# LED_STRIP.net
KiCad netlist of a schematic drawn in EAGLE
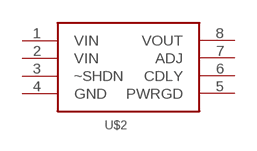
[diagram p0: schematic, sheet 1, part 1 of 2]
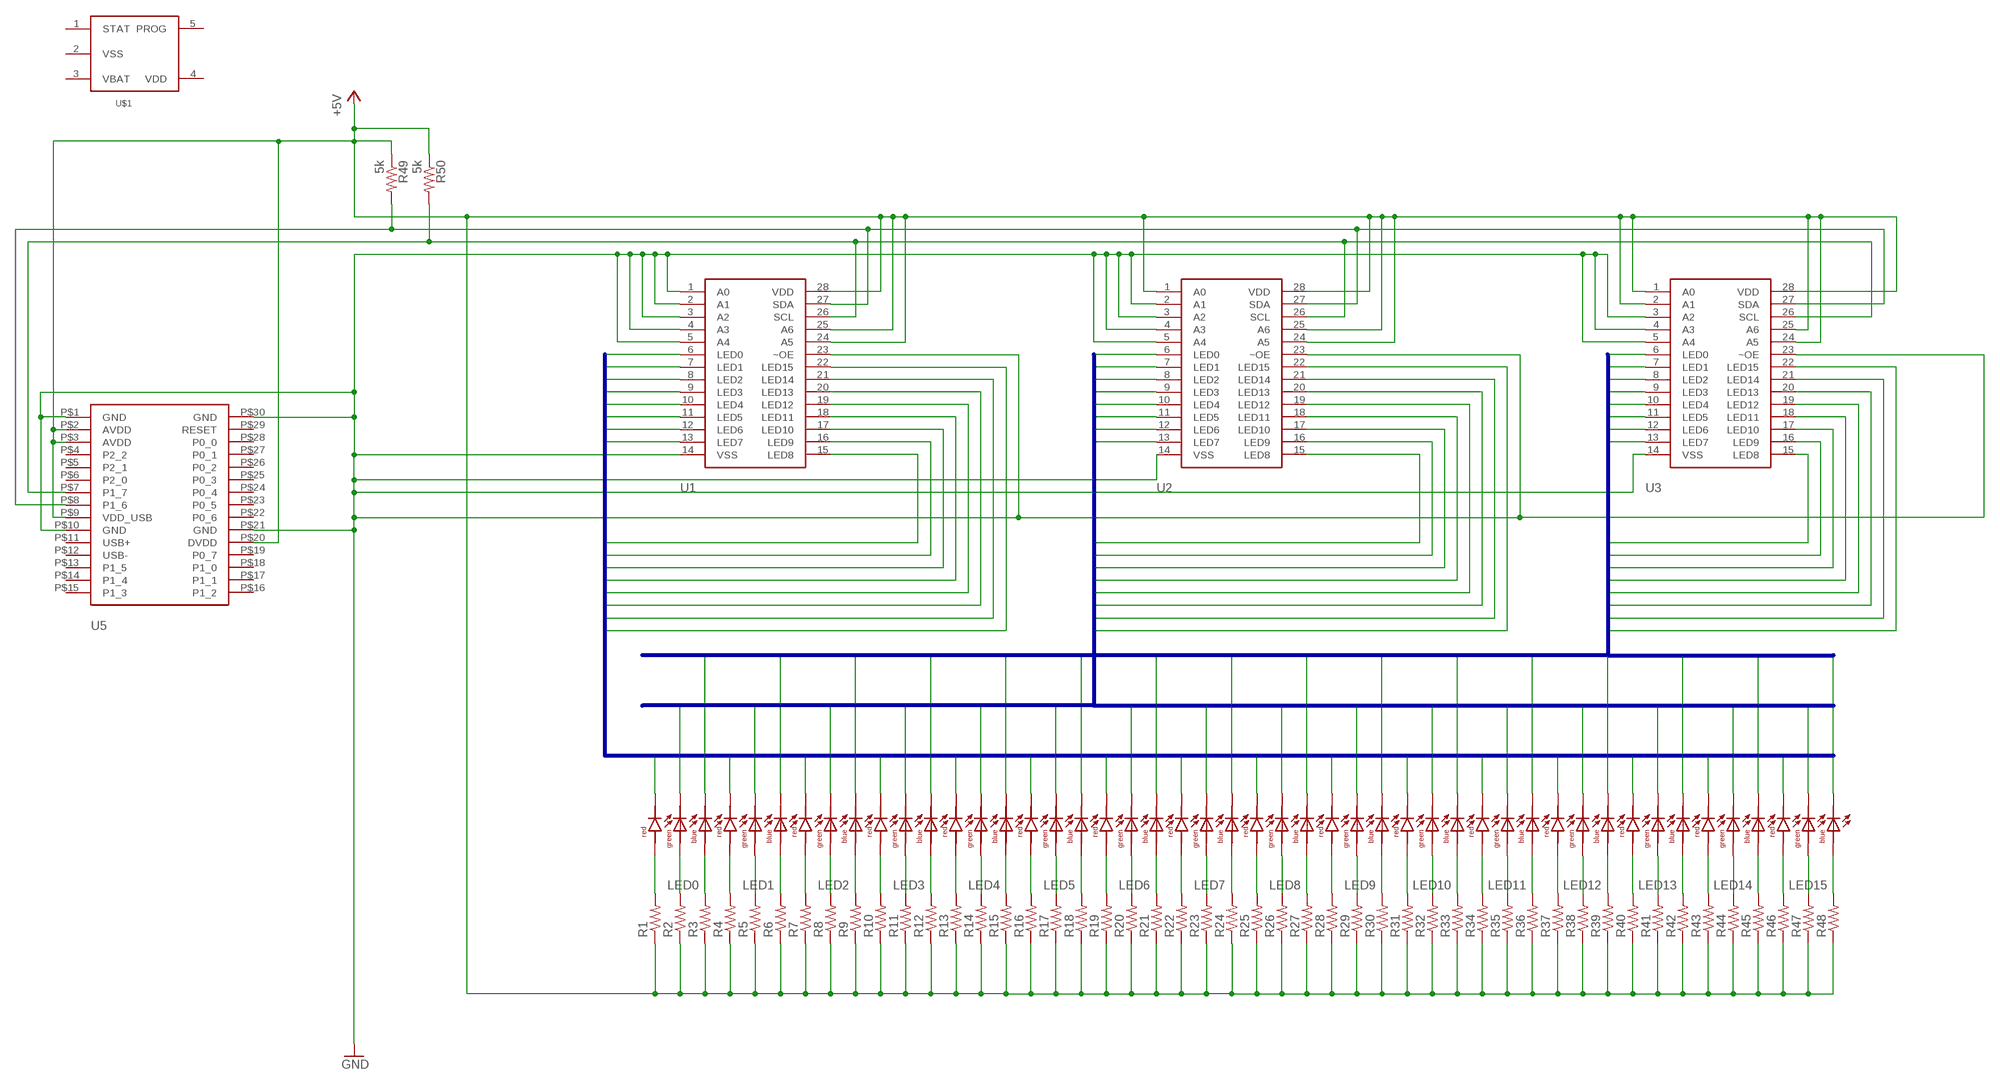
[diagram p1: schematic, sheet 1, part 2 of 2]

(export (version "E")
  (design (tool "Eeschema 10.0.6"))
  (components
    (comp (ref "LED0")
      (value "LED_RGB")
      (footprint "eagle-import:6-PLCC")
      (libsource (lib "eagle-import") (part "LED_RGB"))
    )
    (comp (ref "LED1")
      (value "LED_RGB")
      (footprint "eagle-import:6-PLCC")
      (libsource (lib "eagle-import") (part "LED_RGB"))
    )
    (comp (ref "LED2")
      (value "LED_RGB")
      (footprint "eagle-import:6-PLCC")
      (libsource (lib "eagle-import") (part "LED_RGB"))
    )
    (comp (ref "LED3")
      (value "LED_RGB")
      (footprint "eagle-import:6-PLCC")
      (libsource (lib "eagle-import") (part "LED_RGB"))
    )
    (comp (ref "LED4")
      (value "LED_RGB")
      (footprint "eagle-import:6-PLCC")
      (libsource (lib "eagle-import") (part "LED_RGB"))
    )
    (comp (ref "LED5")
      (value "LED_RGB")
      (footprint "eagle-import:6-PLCC")
      (libsource (lib "eagle-import") (part "LED_RGB"))
    )
    (comp (ref "LED6")
      (value "LED_RGB")
      (footprint "eagle-import:6-PLCC")
      (libsource (lib "eagle-import") (part "LED_RGB"))
    )
    (comp (ref "LED7")
      (value "LED_RGB")
      (footprint "eagle-import:6-PLCC")
      (libsource (lib "eagle-import") (part "LED_RGB"))
    )
    (comp (ref "LED8")
      (value "LED_RGB")
      (footprint "eagle-import:6-PLCC")
      (libsource (lib "eagle-import") (part "LED_RGB"))
    )
    (comp (ref "LED9")
      (value "LED_RGB")
      (footprint "eagle-import:6-PLCC")
      (libsource (lib "eagle-import") (part "LED_RGB"))
    )
    (comp (ref "LED10")
      (value "LED_RGB")
      (footprint "eagle-import:6-PLCC")
      (libsource (lib "eagle-import") (part "LED_RGB"))
    )
    (comp (ref "LED11")
      (value "LED_RGB")
      (footprint "eagle-import:6-PLCC")
      (libsource (lib "eagle-import") (part "LED_RGB"))
    )
    (comp (ref "LED12")
      (value "LED_RGB")
      (footprint "eagle-import:6-PLCC")
      (libsource (lib "eagle-import") (part "LED_RGB"))
    )
    (comp (ref "LED13")
      (value "LED_RGB")
      (footprint "eagle-import:6-PLCC")
      (libsource (lib "eagle-import") (part "LED_RGB"))
    )
    (comp (ref "LED14")
      (value "LED_RGB")
      (footprint "eagle-import:6-PLCC")
      (libsource (lib "eagle-import") (part "LED_RGB"))
    )
    (comp (ref "LED15")
      (value "LED_RGB")
      (footprint "eagle-import:6-PLCC")
      (libsource (lib "eagle-import") (part "LED_RGB"))
    )
    (comp (ref "R1")
      (value "R0402")
      (footprint "eagle-import:0402")
      (libsource (lib "eagle-import") (part "R0402"))
    )
    (comp (ref "R2")
      (value "R0402")
      (footprint "eagle-import:0402")
      (libsource (lib "eagle-import") (part "R0402"))
    )
    (comp (ref "R3")
      (value "R0402")
      (footprint "eagle-import:0402")
      (libsource (lib "eagle-import") (part "R0402"))
    )
    (comp (ref "R4")
      (value "R0402")
      (footprint "eagle-import:0402")
      (libsource (lib "eagle-import") (part "R0402"))
    )
    (comp (ref "R5")
      (value "R0402")
      (footprint "eagle-import:0402")
      (libsource (lib "eagle-import") (part "R0402"))
    )
    (comp (ref "R6")
      (value "R0402")
      (footprint "eagle-import:0402")
      (libsource (lib "eagle-import") (part "R0402"))
    )
    (comp (ref "R7")
      (value "R0402")
      (footprint "eagle-import:0402")
      (libsource (lib "eagle-import") (part "R0402"))
    )
    (comp (ref "R8")
      (value "R0402")
      (footprint "eagle-import:0402")
      (libsource (lib "eagle-import") (part "R0402"))
    )
    (comp (ref "R9")
      (value "R0402")
      (footprint "eagle-import:0402")
      (libsource (lib "eagle-import") (part "R0402"))
    )
    (comp (ref "R10")
      (value "R0402")
      (footprint "eagle-import:0402")
      (libsource (lib "eagle-import") (part "R0402"))
    )
    (comp (ref "R11")
      (value "R0402")
      (footprint "eagle-import:0402")
      (libsource (lib "eagle-import") (part "R0402"))
    )
    (comp (ref "R12")
      (value "R0402")
      (footprint "eagle-import:0402")
      (libsource (lib "eagle-import") (part "R0402"))
    )
    (comp (ref "R13")
      (value "R0402")
      (footprint "eagle-import:0402")
      (libsource (lib "eagle-import") (part "R0402"))
    )
    (comp (ref "R14")
      (value "R0402")
      (footprint "eagle-import:0402")
      (libsource (lib "eagle-import") (part "R0402"))
    )
    (comp (ref "R15")
      (value "R0402")
      (footprint "eagle-import:0402")
      (libsource (lib "eagle-import") (part "R0402"))
    )
    (comp (ref "R16")
      (value "R0402")
      (footprint "eagle-import:0402")
      (libsource (lib "eagle-import") (part "R0402"))
    )
    (comp (ref "R17")
      (value "R0402")
      (footprint "eagle-import:0402")
      (libsource (lib "eagle-import") (part "R0402"))
    )
    (comp (ref "R18")
      (value "R0402")
      (footprint "eagle-import:0402")
      (libsource (lib "eagle-import") (part "R0402"))
    )
    (comp (ref "R19")
      (value "R0402")
      (footprint "eagle-import:0402")
      (libsource (lib "eagle-import") (part "R0402"))
    )
    (comp (ref "R20")
      (value "R0402")
      (footprint "eagle-import:0402")
      (libsource (lib "eagle-import") (part "R0402"))
    )
    (comp (ref "R21")
      (value "R0402")
      (footprint "eagle-import:0402")
      (libsource (lib "eagle-import") (part "R0402"))
    )
    (comp (ref "R22")
      (value "R0402")
      (footprint "eagle-import:0402")
      (libsource (lib "eagle-import") (part "R0402"))
    )
    (comp (ref "R23")
      (value "R0402")
      (footprint "eagle-import:0402")
      (libsource (lib "eagle-import") (part "R0402"))
    )
    (comp (ref "R24")
      (value "R0402")
      (footprint "eagle-import:0402")
      (libsource (lib "eagle-import") (part "R0402"))
    )
    (comp (ref "R25")
      (value "R0402")
      (footprint "eagle-import:0402")
      (libsource (lib "eagle-import") (part "R0402"))
    )
    (comp (ref "R26")
      (value "R0402")
      (footprint "eagle-import:0402")
      (libsource (lib "eagle-import") (part "R0402"))
    )
    (comp (ref "R27")
      (value "R0402")
      (footprint "eagle-import:0402")
      (libsource (lib "eagle-import") (part "R0402"))
    )
    (comp (ref "R28")
      (value "R0402")
      (footprint "eagle-import:0402")
      (libsource (lib "eagle-import") (part "R0402"))
    )
    (comp (ref "R29")
      (value "R0402")
      (footprint "eagle-import:0402")
      (libsource (lib "eagle-import") (part "R0402"))
    )
    (comp (ref "R30")
      (value "R0402")
      (footprint "eagle-import:0402")
      (libsource (lib "eagle-import") (part "R0402"))
    )
    (comp (ref "R31")
      (value "R0402")
      (footprint "eagle-import:0402")
      (libsource (lib "eagle-import") (part "R0402"))
    )
    (comp (ref "R32")
      (value "R0402")
      (footprint "eagle-import:0402")
      (libsource (lib "eagle-import") (part "R0402"))
    )
    (comp (ref "R33")
      (value "R0402")
      (footprint "eagle-import:0402")
      (libsource (lib "eagle-import") (part "R0402"))
    )
    (comp (ref "R34")
      (value "R0402")
      (footprint "eagle-import:0402")
      (libsource (lib "eagle-import") (part "R0402"))
    )
    (comp (ref "R35")
      (value "R0402")
      (footprint "eagle-import:0402")
      (libsource (lib "eagle-import") (part "R0402"))
    )
    (comp (ref "R36")
      (value "R0402")
      (footprint "eagle-import:0402")
      (libsource (lib "eagle-import") (part "R0402"))
    )
    (comp (ref "R37")
      (value "R0402")
      (footprint "eagle-import:0402")
      (libsource (lib "eagle-import") (part "R0402"))
    )
    (comp (ref "R38")
      (value "R0402")
      (footprint "eagle-import:0402")
      (libsource (lib "eagle-import") (part "R0402"))
    )
    (comp (ref "R39")
      (value "R0402")
      (footprint "eagle-import:0402")
      (libsource (lib "eagle-import") (part "R0402"))
    )
    (comp (ref "R40")
      (value "R0402")
      (footprint "eagle-import:0402")
      (libsource (lib "eagle-import") (part "R0402"))
    )
    (comp (ref "R41")
      (value "R0402")
      (footprint "eagle-import:0402")
      (libsource (lib "eagle-import") (part "R0402"))
    )
    (comp (ref "R42")
      (value "R0402")
      (footprint "eagle-import:0402")
      (libsource (lib "eagle-import") (part "R0402"))
    )
    (comp (ref "R43")
      (value "R0402")
      (footprint "eagle-import:0402")
      (libsource (lib "eagle-import") (part "R0402"))
    )
    (comp (ref "R44")
      (value "R0402")
      (footprint "eagle-import:0402")
      (libsource (lib "eagle-import") (part "R0402"))
    )
    (comp (ref "R45")
      (value "R0402")
      (footprint "eagle-import:0402")
      (libsource (lib "eagle-import") (part "R0402"))
    )
    (comp (ref "R46")
      (value "R0402")
      (footprint "eagle-import:0402")
      (libsource (lib "eagle-import") (part "R0402"))
    )
    (comp (ref "R47")
      (value "R0402")
      (footprint "eagle-import:0402")
      (libsource (lib "eagle-import") (part "R0402"))
    )
    (comp (ref "R48")
      (value "R0402")
      (footprint "eagle-import:0402")
      (libsource (lib "eagle-import") (part "R0402"))
    )
    (comp (ref "R49")
      (value "5k")
      (footprint "eagle-import:0402")
      (libsource (lib "eagle-import") (part "R0402"))
    )
    (comp (ref "R50")
      (value "5k")
      (footprint "eagle-import:0402")
      (libsource (lib "eagle-import") (part "R0402"))
    )
    (comp (ref "U$1")
      (value "MCP73831")
      (footprint "eagle-import:SOT-23")
      (libsource (lib "eagle-import") (part "MCP73831"))
    )
    (comp (ref "U$2")
      (value "MCP1727")
      (footprint "eagle-import:8-SOIC")
      (libsource (lib "eagle-import") (part "MCP1727"))
    )
    (comp (ref "U1")
      (value "PCA9635")
      (footprint "eagle-import:TSSOP28")
      (libsource (lib "eagle-import") (part "PCA9635"))
    )
    (comp (ref "U2")
      (value "PCA9635")
      (footprint "eagle-import:TSSOP28")
      (libsource (lib "eagle-import") (part "PCA9635"))
    )
    (comp (ref "U3")
      (value "PCA9635")
      (footprint "eagle-import:TSSOP28")
      (libsource (lib "eagle-import") (part "PCA9635"))
    )
    (comp (ref "U5")
      (value "BLE112")
      (footprint "eagle-import:BLE112")
      (libsource (lib "eagle-import") (part "BLE112"))
    )
  )
  (nets
    (net (code "1") (name "+5V") (class "Default")
      (node (ref "R1") (pin "P$1") (pinfunction "1_P$1") (pintype "passive"))
      (node (ref "R10") (pin "P$1") (pinfunction "1_P$1") (pintype "passive"))
      (node (ref "R11") (pin "P$1") (pinfunction "1_P$1") (pintype "passive"))
      (node (ref "R12") (pin "P$1") (pinfunction "1_P$1") (pintype "passive"))
      (node (ref "R13") (pin "P$1") (pinfunction "1_P$1") (pintype "passive"))
      (node (ref "R14") (pin "P$1") (pinfunction "1_P$1") (pintype "passive"))
      (node (ref "R15") (pin "P$1") (pinfunction "1_P$1") (pintype "passive"))
      (node (ref "R16") (pin "P$1") (pinfunction "1_P$1") (pintype "passive"))
      (node (ref "R17") (pin "P$1") (pinfunction "1_P$1") (pintype "passive"))
      (node (ref "R18") (pin "P$1") (pinfunction "1_P$1") (pintype "passive"))
      (node (ref "R19") (pin "P$1") (pinfunction "1_P$1") (pintype "passive"))
      (node (ref "R2") (pin "P$1") (pinfunction "1_P$1") (pintype "passive"))
      (node (ref "R20") (pin "P$1") (pinfunction "1_P$1") (pintype "passive"))
      (node (ref "R21") (pin "P$1") (pinfunction "1_P$1") (pintype "passive"))
      (node (ref "R22") (pin "P$1") (pinfunction "1_P$1") (pintype "passive"))
      (node (ref "R23") (pin "P$1") (pinfunction "1_P$1") (pintype "passive"))
      (node (ref "R24") (pin "P$1") (pinfunction "1_P$1") (pintype "passive"))
      (node (ref "R25") (pin "P$1") (pinfunction "1_P$1") (pintype "passive"))
      (node (ref "R26") (pin "P$1") (pinfunction "1_P$1") (pintype "passive"))
      (node (ref "R27") (pin "P$1") (pinfunction "1_P$1") (pintype "passive"))
      (node (ref "R28") (pin "P$1") (pinfunction "1_P$1") (pintype "passive"))
      (node (ref "R29") (pin "P$1") (pinfunction "1_P$1") (pintype "passive"))
      (node (ref "R3") (pin "P$1") (pinfunction "1_P$1") (pintype "passive"))
      (node (ref "R30") (pin "P$1") (pinfunction "1_P$1") (pintype "passive"))
      (node (ref "R31") (pin "P$1") (pinfunction "1_P$1") (pintype "passive"))
      (node (ref "R32") (pin "P$1") (pinfunction "1_P$1") (pintype "passive"))
      (node (ref "R33") (pin "P$1") (pinfunction "1_P$1") (pintype "passive"))
      (node (ref "R34") (pin "P$1") (pinfunction "1_P$1") (pintype "passive"))
      (node (ref "R35") (pin "P$1") (pinfunction "1_P$1") (pintype "passive"))
      (node (ref "R36") (pin "P$1") (pinfunction "1_P$1") (pintype "passive"))
      (node (ref "R37") (pin "P$1") (pinfunction "1_P$1") (pintype "passive"))
      (node (ref "R38") (pin "P$1") (pinfunction "1_P$1") (pintype "passive"))
      (node (ref "R39") (pin "P$1") (pinfunction "1_P$1") (pintype "passive"))
      (node (ref "R4") (pin "P$1") (pinfunction "1_P$1") (pintype "passive"))
      (node (ref "R40") (pin "P$1") (pinfunction "1_P$1") (pintype "passive"))
      (node (ref "R41") (pin "P$1") (pinfunction "1_P$1") (pintype "passive"))
      (node (ref "R42") (pin "P$1") (pinfunction "1_P$1") (pintype "passive"))
      (node (ref "R43") (pin "P$1") (pinfunction "1_P$1") (pintype "passive"))
      (node (ref "R44") (pin "P$1") (pinfunction "1_P$1") (pintype "passive"))
      (node (ref "R45") (pin "P$1") (pinfunction "1_P$1") (pintype "passive"))
      (node (ref "R46") (pin "P$1") (pinfunction "1_P$1") (pintype "passive"))
      (node (ref "R47") (pin "P$1") (pinfunction "1_P$1") (pintype "passive"))
      (node (ref "R48") (pin "P$1") (pinfunction "1_P$1") (pintype "passive"))
      (node (ref "R49") (pin "P$1") (pinfunction "1_P$1") (pintype "passive"))
      (node (ref "R5") (pin "P$1") (pinfunction "1_P$1") (pintype "passive"))
      (node (ref "R50") (pin "P$1") (pinfunction "1_P$1") (pintype "passive"))
      (node (ref "R6") (pin "P$1") (pinfunction "1_P$1") (pintype "passive"))
      (node (ref "R7") (pin "P$1") (pinfunction "1_P$1") (pintype "passive"))
      (node (ref "R8") (pin "P$1") (pinfunction "1_P$1") (pintype "passive"))
      (node (ref "R9") (pin "P$1") (pinfunction "1_P$1") (pintype "passive"))
      (node (ref "U1") (pin "24") (pinfunction "A5_24") (pintype "bidirectional"))
      (node (ref "U1") (pin "25") (pinfunction "A6_25") (pintype "bidirectional"))
      (node (ref "U1") (pin "28") (pinfunction "VDD_28") (pintype "bidirectional"))
      (node (ref "U2") (pin "1") (pinfunction "A0_1") (pintype "bidirectional"))
      (node (ref "U2") (pin "24") (pinfunction "A5_24") (pintype "bidirectional"))
      (node (ref "U2") (pin "25") (pinfunction "A6_25") (pintype "bidirectional"))
      (node (ref "U2") (pin "28") (pinfunction "VDD_28") (pintype "bidirectional"))
      (node (ref "U3") (pin "1") (pinfunction "A0_1") (pintype "bidirectional"))
      (node (ref "U3") (pin "2") (pinfunction "A1_2") (pintype "bidirectional"))
      (node (ref "U3") (pin "24") (pinfunction "A5_24") (pintype "bidirectional"))
      (node (ref "U3") (pin "25") (pinfunction "A6_25") (pintype "bidirectional"))
      (node (ref "U3") (pin "28") (pinfunction "VDD_28") (pintype "bidirectional"))
      (node (ref "U5") (pin "P$2") (pinfunction "AVDD_P$2") (pintype "bidirectional"))
      (node (ref "U5") (pin "P$20") (pinfunction "DVDD_P$20") (pintype "bidirectional"))
      (node (ref "U5") (pin "P$3") (pinfunction "AVDD_P$3") (pintype "bidirectional"))
      (node (ref "U5") (pin "P$9") (pinfunction "VDD_USB_P$9") (pintype "bidirectional"))
    )
    (net (code "2") (name "/BLUE0") (class "Default")
      (node (ref "LED0") (pin "1") (pinfunction "1_1") (pintype "passive"))
      (node (ref "U3") (pin "6") (pinfunction "LED0_6") (pintype "bidirectional"))
    )
    (net (code "3") (name "/BLUE1") (class "Default")
      (node (ref "LED1") (pin "1") (pinfunction "1_1") (pintype "passive"))
      (node (ref "U3") (pin "7") (pinfunction "LED1_7") (pintype "bidirectional"))
    )
    (net (code "4") (name "/BLUE2") (class "Default")
      (node (ref "LED2") (pin "1") (pinfunction "1_1") (pintype "passive"))
      (node (ref "U3") (pin "8") (pinfunction "LED2_8") (pintype "bidirectional"))
    )
    (net (code "5") (name "/BLUE3") (class "Default")
      (node (ref "LED3") (pin "1") (pinfunction "1_1") (pintype "passive"))
      (node (ref "U3") (pin "9") (pinfunction "LED3_9") (pintype "bidirectional"))
    )
    (net (code "6") (name "/BLUE4") (class "Default")
      (node (ref "LED4") (pin "1") (pinfunction "1_1") (pintype "passive"))
      (node (ref "U3") (pin "10") (pinfunction "LED4_10") (pintype "bidirectional"))
    )
    (net (code "7") (name "/BLUE5") (class "Default")
      (node (ref "LED5") (pin "1") (pinfunction "1_1") (pintype "passive"))
      (node (ref "U3") (pin "11") (pinfunction "LED5_11") (pintype "bidirectional"))
    )
    (net (code "8") (name "/BLUE6") (class "Default")
      (node (ref "LED6") (pin "1") (pinfunction "1_1") (pintype "passive"))
      (node (ref "U3") (pin "12") (pinfunction "LED6_12") (pintype "bidirectional"))
    )
    (net (code "9") (name "/BLUE7") (class "Default")
      (node (ref "LED7") (pin "1") (pinfunction "1_1") (pintype "passive"))
      (node (ref "U3") (pin "13") (pinfunction "LED7_13") (pintype "bidirectional"))
    )
    (net (code "10") (name "/BLUE8") (class "Default")
      (node (ref "LED8") (pin "1") (pinfunction "1_1") (pintype "passive"))
      (node (ref "U3") (pin "15") (pinfunction "LED8_15") (pintype "bidirectional"))
    )
    (net (code "11") (name "/BLUE9") (class "Default")
      (node (ref "LED9") (pin "1") (pinfunction "1_1") (pintype "passive"))
      (node (ref "U3") (pin "16") (pinfunction "LED9_16") (pintype "bidirectional"))
    )
    (net (code "12") (name "/BLUE10") (class "Default")
      (node (ref "LED10") (pin "1") (pinfunction "1_1") (pintype "passive"))
      (node (ref "U3") (pin "17") (pinfunction "LED10_17") (pintype "bidirectional"))
    )
    (net (code "13") (name "/BLUE11") (class "Default")
      (node (ref "LED11") (pin "1") (pinfunction "1_1") (pintype "passive"))
      (node (ref "U3") (pin "18") (pinfunction "LED11_18") (pintype "bidirectional"))
    )
    (net (code "14") (name "/BLUE12") (class "Default")
      (node (ref "LED12") (pin "1") (pinfunction "1_1") (pintype "passive"))
      (node (ref "U3") (pin "19") (pinfunction "LED12_19") (pintype "bidirectional"))
    )
    (net (code "15") (name "/BLUE13") (class "Default")
      (node (ref "LED13") (pin "1") (pinfunction "1_1") (pintype "passive"))
      (node (ref "U3") (pin "20") (pinfunction "LED13_20") (pintype "bidirectional"))
    )
    (net (code "16") (name "/BLUE14") (class "Default")
      (node (ref "LED14") (pin "1") (pinfunction "1_1") (pintype "passive"))
      (node (ref "U3") (pin "21") (pinfunction "LED14_21") (pintype "bidirectional"))
    )
    (net (code "17") (name "/BLUE15") (class "Default")
      (node (ref "LED15") (pin "1") (pinfunction "1_1") (pintype "passive"))
      (node (ref "U3") (pin "22") (pinfunction "LED15_22") (pintype "bidirectional"))
    )
    (net (code "18") (name "/GREEN0") (class "Default")
      (node (ref "LED0") (pin "2") (pinfunction "2_2") (pintype "passive"))
      (node (ref "U2") (pin "6") (pinfunction "LED0_6") (pintype "bidirectional"))
    )
    (net (code "19") (name "/GREEN1") (class "Default")
      (node (ref "LED1") (pin "2") (pinfunction "2_2") (pintype "passive"))
      (node (ref "U2") (pin "7") (pinfunction "LED1_7") (pintype "bidirectional"))
    )
    (net (code "20") (name "/GREEN2") (class "Default")
      (node (ref "LED2") (pin "2") (pinfunction "2_2") (pintype "passive"))
      (node (ref "U2") (pin "8") (pinfunction "LED2_8") (pintype "bidirectional"))
    )
    (net (code "21") (name "/GREEN3") (class "Default")
      (node (ref "LED3") (pin "2") (pinfunction "2_2") (pintype "passive"))
      (node (ref "U2") (pin "9") (pinfunction "LED3_9") (pintype "bidirectional"))
    )
    (net (code "22") (name "/GREEN4") (class "Default")
      (node (ref "LED4") (pin "2") (pinfunction "2_2") (pintype "passive"))
      (node (ref "U2") (pin "10") (pinfunction "LED4_10") (pintype "bidirectional"))
    )
    (net (code "23") (name "/GREEN5") (class "Default")
      (node (ref "LED5") (pin "2") (pinfunction "2_2") (pintype "passive"))
      (node (ref "U2") (pin "11") (pinfunction "LED5_11") (pintype "bidirectional"))
    )
    (net (code "24") (name "/GREEN6") (class "Default")
      (node (ref "LED6") (pin "2") (pinfunction "2_2") (pintype "passive"))
      (node (ref "U2") (pin "12") (pinfunction "LED6_12") (pintype "bidirectional"))
    )
    (net (code "25") (name "/GREEN7") (class "Default")
      (node (ref "LED7") (pin "2") (pinfunction "2_2") (pintype "passive"))
      (node (ref "U2") (pin "13") (pinfunction "LED7_13") (pintype "bidirectional"))
    )
    (net (code "26") (name "/GREEN8") (class "Default")
      (node (ref "LED8") (pin "2") (pinfunction "2_2") (pintype "passive"))
      (node (ref "U2") (pin "15") (pinfunction "LED8_15") (pintype "bidirectional"))
    )
    (net (code "27") (name "/GREEN9") (class "Default")
      (node (ref "LED9") (pin "2") (pinfunction "2_2") (pintype "passive"))
      (node (ref "U2") (pin "16") (pinfunction "LED9_16") (pintype "bidirectional"))
    )
    (net (code "28") (name "/GREEN10") (class "Default")
      (node (ref "LED10") (pin "2") (pinfunction "2_2") (pintype "passive"))
      (node (ref "U2") (pin "17") (pinfunction "LED10_17") (pintype "bidirectional"))
    )
    (net (code "29") (name "/GREEN11") (class "Default")
      (node (ref "LED11") (pin "2") (pinfunction "2_2") (pintype "passive"))
      (node (ref "U2") (pin "18") (pinfunction "LED11_18") (pintype "bidirectional"))
    )
    (net (code "30") (name "/GREEN12") (class "Default")
      (node (ref "LED12") (pin "2") (pinfunction "2_2") (pintype "passive"))
      (node (ref "U2") (pin "19") (pinfunction "LED12_19") (pintype "bidirectional"))
    )
    (net (code "31") (name "/GREEN13") (class "Default")
      (node (ref "LED13") (pin "2") (pinfunction "2_2") (pintype "passive"))
      (node (ref "U2") (pin "20") (pinfunction "LED13_20") (pintype "bidirectional"))
    )
    (net (code "32") (name "/GREEN14") (class "Default")
      (node (ref "LED14") (pin "2") (pinfunction "2_2") (pintype "passive"))
      (node (ref "U2") (pin "21") (pinfunction "LED14_21") (pintype "bidirectional"))
    )
    (net (code "33") (name "/GREEN15") (class "Default")
      (node (ref "LED15") (pin "2") (pinfunction "2_2") (pintype "passive"))
      (node (ref "U2") (pin "22") (pinfunction "LED15_22") (pintype "bidirectional"))
    )
    (net (code "34") (name "/RED0") (class "Default")
      (node (ref "LED0") (pin "3") (pinfunction "3_3") (pintype "passive"))
      (node (ref "U1") (pin "6") (pinfunction "LED0_6") (pintype "bidirectional"))
    )
    (net (code "35") (name "/RED1") (class "Default")
      (node (ref "LED1") (pin "3") (pinfunction "3_3") (pintype "passive"))
      (node (ref "U1") (pin "7") (pinfunction "LED1_7") (pintype "bidirectional"))
    )
    (net (code "36") (name "/RED2") (class "Default")
      (node (ref "LED2") (pin "3") (pinfunction "3_3") (pintype "passive"))
      (node (ref "U1") (pin "8") (pinfunction "LED2_8") (pintype "bidirectional"))
    )
    (net (code "37") (name "/RED3") (class "Default")
      (node (ref "LED3") (pin "3") (pinfunction "3_3") (pintype "passive"))
      (node (ref "U1") (pin "9") (pinfunction "LED3_9") (pintype "bidirectional"))
    )
    (net (code "38") (name "/RED4") (class "Default")
      (node (ref "LED4") (pin "3") (pinfunction "3_3") (pintype "passive"))
      (node (ref "U1") (pin "10") (pinfunction "LED4_10") (pintype "bidirectional"))
    )
    (net (code "39") (name "/RED5") (class "Default")
      (node (ref "LED5") (pin "3") (pinfunction "3_3") (pintype "passive"))
      (node (ref "U1") (pin "11") (pinfunction "LED5_11") (pintype "bidirectional"))
    )
    (net (code "40") (name "/RED6") (class "Default")
      (node (ref "LED6") (pin "3") (pinfunction "3_3") (pintype "passive"))
      (node (ref "U1") (pin "12") (pinfunction "LED6_12") (pintype "bidirectional"))
    )
    (net (code "41") (name "/RED7") (class "Default")
      (node (ref "LED7") (pin "3") (pinfunction "3_3") (pintype "passive"))
      (node (ref "U1") (pin "13") (pinfunction "LED7_13") (pintype "bidirectional"))
    )
    (net (code "42") (name "/RED8") (class "Default")
      (node (ref "LED8") (pin "3") (pinfunction "3_3") (pintype "passive"))
      (node (ref "U1") (pin "15") (pinfunction "LED8_15") (pintype "bidirectional"))
    )
    (net (code "43") (name "/RED9") (class "Default")
      (node (ref "LED9") (pin "3") (pinfunction "3_3") (pintype "passive"))
      (node (ref "U1") (pin "16") (pinfunction "LED9_16") (pintype "bidirectional"))
    )
    (net (code "44") (name "/RED10") (class "Default")
      (node (ref "LED10") (pin "3") (pinfunction "3_3") (pintype "passive"))
      (node (ref "U1") (pin "17") (pinfunction "LED10_17") (pintype "bidirectional"))
    )
    (net (code "45") (name "/RED11") (class "Default")
      (node (ref "LED11") (pin "3") (pinfunction "3_3") (pintype "passive"))
      (node (ref "U1") (pin "18") (pinfunction "LED11_18") (pintype "bidirectional"))
    )
    (net (code "46") (name "/RED12") (class "Default")
      (node (ref "LED12") (pin "3") (pinfunction "3_3") (pintype "passive"))
      (node (ref "U1") (pin "19") (pinfunction "LED12_19") (pintype "bidirectional"))
    )
    (net (code "47") (name "/RED13") (class "Default")
      (node (ref "LED13") (pin "3") (pinfunction "3_3") (pintype "passive"))
      (node (ref "U1") (pin "20") (pinfunction "LED13_20") (pintype "bidirectional"))
    )
    (net (code "48") (name "/RED14") (class "Default")
      (node (ref "LED14") (pin "3") (pinfunction "3_3") (pintype "passive"))
      (node (ref "U1") (pin "21") (pinfunction "LED14_21") (pintype "bidirectional"))
    )
    (net (code "49") (name "/RED15") (class "Default")
      (node (ref "LED15") (pin "3") (pinfunction "3_3") (pintype "passive"))
      (node (ref "U1") (pin "22") (pinfunction "LED15_22") (pintype "bidirectional"))
    )
    (net (code "50") (name "GND") (class "Default")
      (node (ref "U1") (pin "1") (pinfunction "A0_1") (pintype "bidirectional"))
      (node (ref "U1") (pin "14") (pinfunction "VSS_14") (pintype "bidirectional"))
      (node (ref "U1") (pin "2") (pinfunction "A1_2") (pintype "bidirectional"))
      (node (ref "U1") (pin "23") (pinfunction "~{OE}_23") (pintype "bidirectional"))
      (node (ref "U1") (pin "3") (pinfunction "A2_3") (pintype "bidirectional"))
      (node (ref "U1") (pin "4") (pinfunction "A3_4") (pintype "bidirectional"))
      (node (ref "U1") (pin "5") (pinfunction "A4_5") (pintype "bidirectional"))
      (node (ref "U2") (pin "14") (pinfunction "VSS_14") (pintype "bidirectional"))
      (node (ref "U2") (pin "2") (pinfunction "A1_2") (pintype "bidirectional"))
      (node (ref "U2") (pin "23") (pinfunction "~{OE}_23") (pintype "bidirectional"))
      (node (ref "U2") (pin "3") (pinfunction "A2_3") (pintype "bidirectional"))
      (node (ref "U2") (pin "4") (pinfunction "A3_4") (pintype "bidirectional"))
      (node (ref "U2") (pin "5") (pinfunction "A4_5") (pintype "bidirectional"))
      (node (ref "U3") (pin "14") (pinfunction "VSS_14") (pintype "bidirectional"))
      (node (ref "U3") (pin "23") (pinfunction "~{OE}_23") (pintype "bidirectional"))
      (node (ref "U3") (pin "3") (pinfunction "A2_3") (pintype "bidirectional"))
      (node (ref "U3") (pin "4") (pinfunction "A3_4") (pintype "bidirectional"))
      (node (ref "U3") (pin "5") (pinfunction "A4_5") (pintype "bidirectional"))
      (node (ref "U5") (pin "P$1") (pinfunction "GND_P$1") (pintype "bidirectional"))
      (node (ref "U5") (pin "P$10") (pinfunction "GND_P$10") (pintype "bidirectional"))
      (node (ref "U5") (pin "P$21") (pinfunction "GND_P$21") (pintype "bidirectional"))
      (node (ref "U5") (pin "P$30") (pinfunction "GND_P$30") (pintype "bidirectional"))
    )
    (net (code "51") (name "Net-(R1-2)") (class "Default")
      (node (ref "LED0") (pin "4") (pinfunction "4_4") (pintype "passive"))
      (node (ref "R1") (pin "P$2") (pinfunction "2_P$2") (pintype "passive"))
    )
    (net (code "52") (name "Net-(R2-2)") (class "Default")
      (node (ref "LED0") (pin "5") (pinfunction "5_5") (pintype "passive"))
      (node (ref "R2") (pin "P$2") (pinfunction "2_P$2") (pintype "passive"))
    )
    (net (code "53") (name "Net-(R3-2)") (class "Default")
      (node (ref "LED0") (pin "6") (pinfunction "6_6") (pintype "passive"))
      (node (ref "R3") (pin "P$2") (pinfunction "2_P$2") (pintype "passive"))
    )
    (net (code "54") (name "Net-(R4-2)") (class "Default")
      (node (ref "LED1") (pin "4") (pinfunction "4_4") (pintype "passive"))
      (node (ref "R4") (pin "P$2") (pinfunction "2_P$2") (pintype "passive"))
    )
    (net (code "55") (name "Net-(R5-2)") (class "Default")
      (node (ref "LED1") (pin "5") (pinfunction "5_5") (pintype "passive"))
      (node (ref "R5") (pin "P$2") (pinfunction "2_P$2") (pintype "passive"))
    )
    (net (code "56") (name "Net-(R6-2)") (class "Default")
      (node (ref "LED1") (pin "6") (pinfunction "6_6") (pintype "passive"))
      (node (ref "R6") (pin "P$2") (pinfunction "2_P$2") (pintype "passive"))
    )
    (net (code "57") (name "Net-(R7-2)") (class "Default")
      (node (ref "LED2") (pin "4") (pinfunction "4_4") (pintype "passive"))
      (node (ref "R7") (pin "P$2") (pinfunction "2_P$2") (pintype "passive"))
    )
    (net (code "58") (name "Net-(R8-2)") (class "Default")
      (node (ref "LED2") (pin "5") (pinfunction "5_5") (pintype "passive"))
      (node (ref "R8") (pin "P$2") (pinfunction "2_P$2") (pintype "passive"))
    )
    (net (code "59") (name "Net-(R9-2)") (class "Default")
      (node (ref "LED2") (pin "6") (pinfunction "6_6") (pintype "passive"))
      (node (ref "R9") (pin "P$2") (pinfunction "2_P$2") (pintype "passive"))
    )
    (net (code "60") (name "Net-(R10-2)") (class "Default")
      (node (ref "LED3") (pin "4") (pinfunction "4_4") (pintype "passive"))
      (node (ref "R10") (pin "P$2") (pinfunction "2_P$2") (pintype "passive"))
    )
    (net (code "61") (name "Net-(R11-2)") (class "Default")
      (node (ref "LED3") (pin "5") (pinfunction "5_5") (pintype "passive"))
      (node (ref "R11") (pin "P$2") (pinfunction "2_P$2") (pintype "passive"))
    )
    (net (code "62") (name "Net-(R12-2)") (class "Default")
      (node (ref "LED3") (pin "6") (pinfunction "6_6") (pintype "passive"))
      (node (ref "R12") (pin "P$2") (pinfunction "2_P$2") (pintype "passive"))
    )
    (net (code "63") (name "Net-(R13-2)") (class "Default")
      (node (ref "LED4") (pin "4") (pinfunction "4_4") (pintype "passive"))
      (node (ref "R13") (pin "P$2") (pinfunction "2_P$2") (pintype "passive"))
    )
    (net (code "64") (name "Net-(R14-2)") (class "Default")
      (node (ref "LED4") (pin "5") (pinfunction "5_5") (pintype "passive"))
      (node (ref "R14") (pin "P$2") (pinfunction "2_P$2") (pintype "passive"))
    )
    (net (code "65") (name "Net-(R15-2)") (class "Default")
      (node (ref "LED4") (pin "6") (pinfunction "6_6") (pintype "passive"))
      (node (ref "R15") (pin "P$2") (pinfunction "2_P$2") (pintype "passive"))
    )
    (net (code "66") (name "Net-(R16-2)") (class "Default")
      (node (ref "LED5") (pin "4") (pinfunction "4_4") (pintype "passive"))
      (node (ref "R16") (pin "P$2") (pinfunction "2_P$2") (pintype "passive"))
    )
    (net (code "67") (name "Net-(R17-2)") (class "Default")
      (node (ref "LED5") (pin "5") (pinfunction "5_5") (pintype "passive"))
      (node (ref "R17") (pin "P$2") (pinfunction "2_P$2") (pintype "passive"))
    )
    (net (code "68") (name "Net-(R18-2)") (class "Default")
      (node (ref "LED5") (pin "6") (pinfunction "6_6") (pintype "passive"))
      (node (ref "R18") (pin "P$2") (pinfunction "2_P$2") (pintype "passive"))
    )
    (net (code "69") (name "Net-(R19-2)") (class "Default")
      (node (ref "LED6") (pin "4") (pinfunction "4_4") (pintype "passive"))
      (node (ref "R19") (pin "P$2") (pinfunction "2_P$2") (pintype "passive"))
    )
    (net (code "70") (name "Net-(R20-2)") (class "Default")
      (node (ref "LED6") (pin "5") (pinfunction "5_5") (pintype "passive"))
      (node (ref "R20") (pin "P$2") (pinfunction "2_P$2") (pintype "passive"))
    )
    (net (code "71") (name "Net-(R21-2)") (class "Default")
      (node (ref "LED6") (pin "6") (pinfunction "6_6") (pintype "passive"))
      (node (ref "R21") (pin "P$2") (pinfunction "2_P$2") (pintype "passive"))
    )
    (net (code "72") (name "Net-(R22-2)") (class "Default")
      (node (ref "LED7") (pin "4") (pinfunction "4_4") (pintype "passive"))
      (node (ref "R22") (pin "P$2") (pinfunction "2_P$2") (pintype "passive"))
    )
    (net (code "73") (name "Net-(R23-2)") (class "Default")
      (node (ref "LED7") (pin "5") (pinfunction "5_5") (pintype "passive"))
      (node (ref "R23") (pin "P$2") (pinfunction "2_P$2") (pintype "passive"))
    )
    (net (code "74") (name "Net-(R24-2)") (class "Default")
      (node (ref "LED7") (pin "6") (pinfunction "6_6") (pintype "passive"))
      (node (ref "R24") (pin "P$2") (pinfunction "2_P$2") (pintype "passive"))
    )
    (net (code "75") (name "Net-(R25-2)") (class "Default")
      (node (ref "LED8") (pin "4") (pinfunction "4_4") (pintype "passive"))
      (node (ref "R25") (pin "P$2") (pinfunction "2_P$2") (pintype "passive"))
    )
    (net (code "76") (name "Net-(R26-2)") (class "Default")
      (node (ref "LED8") (pin "5") (pinfunction "5_5") (pintype "passive"))
      (node (ref "R26") (pin "P$2") (pinfunction "2_P$2") (pintype "passive"))
    )
    (net (code "77") (name "Net-(R27-2)") (class "Default")
      (node (ref "LED8") (pin "6") (pinfunction "6_6") (pintype "passive"))
      (node (ref "R27") (pin "P$2") (pinfunction "2_P$2") (pintype "passive"))
    )
    (net (code "78") (name "Net-(R28-2)") (class "Default")
      (node (ref "LED9") (pin "4") (pinfunction "4_4") (pintype "passive"))
      (node (ref "R28") (pin "P$2") (pinfunction "2_P$2") (pintype "passive"))
    )
    (net (code "79") (name "Net-(R29-2)") (class "Default")
      (node (ref "LED9") (pin "5") (pinfunction "5_5") (pintype "passive"))
      (node (ref "R29") (pin "P$2") (pinfunction "2_P$2") (pintype "passive"))
    )
    (net (code "80") (name "Net-(R30-2)") (class "Default")
      (node (ref "LED9") (pin "6") (pinfunction "6_6") (pintype "passive"))
      (node (ref "R30") (pin "P$2") (pinfunction "2_P$2") (pintype "passive"))
    )
    (net (code "81") (name "Net-(R31-2)") (class "Default")
      (node (ref "LED10") (pin "4") (pinfunction "4_4") (pintype "passive"))
      (node (ref "R31") (pin "P$2") (pinfunction "2_P$2") (pintype "passive"))
    )
    (net (code "82") (name "Net-(R32-2)") (class "Default")
      (node (ref "LED10") (pin "5") (pinfunction "5_5") (pintype "passive"))
      (node (ref "R32") (pin "P$2") (pinfunction "2_P$2") (pintype "passive"))
    )
    (net (code "83") (name "Net-(R33-2)") (class "Default")
      (node (ref "LED10") (pin "6") (pinfunction "6_6") (pintype "passive"))
      (node (ref "R33") (pin "P$2") (pinfunction "2_P$2") (pintype "passive"))
    )
    (net (code "84") (name "Net-(R34-2)") (class "Default")
      (node (ref "LED11") (pin "4") (pinfunction "4_4") (pintype "passive"))
      (node (ref "R34") (pin "P$2") (pinfunction "2_P$2") (pintype "passive"))
    )
    (net (code "85") (name "Net-(R35-2)") (class "Default")
      (node (ref "LED11") (pin "5") (pinfunction "5_5") (pintype "passive"))
      (node (ref "R35") (pin "P$2") (pinfunction "2_P$2") (pintype "passive"))
    )
    (net (code "86") (name "Net-(R36-2)") (class "Default")
      (node (ref "LED11") (pin "6") (pinfunction "6_6") (pintype "passive"))
      (node (ref "R36") (pin "P$2") (pinfunction "2_P$2") (pintype "passive"))
    )
    (net (code "87") (name "Net-(R37-2)") (class "Default")
      (node (ref "LED12") (pin "4") (pinfunction "4_4") (pintype "passive"))
      (node (ref "R37") (pin "P$2") (pinfunction "2_P$2") (pintype "passive"))
    )
    (net (code "88") (name "Net-(R38-2)") (class "Default")
      (node (ref "LED12") (pin "5") (pinfunction "5_5") (pintype "passive"))
      (node (ref "R38") (pin "P$2") (pinfunction "2_P$2") (pintype "passive"))
    )
    (net (code "89") (name "Net-(R39-2)") (class "Default")
      (node (ref "LED12") (pin "6") (pinfunction "6_6") (pintype "passive"))
      (node (ref "R39") (pin "P$2") (pinfunction "2_P$2") (pintype "passive"))
    )
    (net (code "90") (name "Net-(R40-2)") (class "Default")
      (node (ref "LED13") (pin "4") (pinfunction "4_4") (pintype "passive"))
      (node (ref "R40") (pin "P$2") (pinfunction "2_P$2") (pintype "passive"))
    )
    (net (code "91") (name "Net-(R41-2)") (class "Default")
      (node (ref "LED13") (pin "5") (pinfunction "5_5") (pintype "passive"))
      (node (ref "R41") (pin "P$2") (pinfunction "2_P$2") (pintype "passive"))
    )
    (net (code "92") (name "Net-(R42-2)") (class "Default")
      (node (ref "LED13") (pin "6") (pinfunction "6_6") (pintype "passive"))
      (node (ref "R42") (pin "P$2") (pinfunction "2_P$2") (pintype "passive"))
    )
    (net (code "93") (name "Net-(R43-2)") (class "Default")
      (node (ref "LED14") (pin "4") (pinfunction "4_4") (pintype "passive"))
      (node (ref "R43") (pin "P$2") (pinfunction "2_P$2") (pintype "passive"))
    )
    (net (code "94") (name "Net-(R44-2)") (class "Default")
      (node (ref "LED14") (pin "5") (pinfunction "5_5") (pintype "passive"))
      (node (ref "R44") (pin "P$2") (pinfunction "2_P$2") (pintype "passive"))
    )
    (net (code "95") (name "Net-(R45-2)") (class "Default")
      (node (ref "LED14") (pin "6") (pinfunction "6_6") (pintype "passive"))
      (node (ref "R45") (pin "P$2") (pinfunction "2_P$2") (pintype "passive"))
    )
    (net (code "96") (name "Net-(R46-2)") (class "Default")
      (node (ref "LED15") (pin "4") (pinfunction "4_4") (pintype "passive"))
      (node (ref "R46") (pin "P$2") (pinfunction "2_P$2") (pintype "passive"))
    )
    (net (code "97") (name "Net-(R47-2)") (class "Default")
      (node (ref "LED15") (pin "5") (pinfunction "5_5") (pintype "passive"))
      (node (ref "R47") (pin "P$2") (pinfunction "2_P$2") (pintype "passive"))
    )
    (net (code "98") (name "Net-(R48-2)") (class "Default")
      (node (ref "LED15") (pin "6") (pinfunction "6_6") (pintype "passive"))
      (node (ref "R48") (pin "P$2") (pinfunction "2_P$2") (pintype "passive"))
    )
    (net (code "99") (name "Net-(R49-2)") (class "Default")
      (node (ref "R49") (pin "P$2") (pinfunction "2_P$2") (pintype "passive"))
      (node (ref "U1") (pin "27") (pinfunction "SDA_27") (pintype "bidirectional"))
      (node (ref "U2") (pin "27") (pinfunction "SDA_27") (pintype "bidirectional"))
      (node (ref "U3") (pin "27") (pinfunction "SDA_27") (pintype "bidirectional"))
      (node (ref "U5") (pin "P$8") (pinfunction "P1_6_P$8") (pintype "bidirectional"))
    )
    (net (code "100") (name "Net-(R50-2)") (class "Default")
      (node (ref "R50") (pin "P$2") (pinfunction "2_P$2") (pintype "passive"))
      (node (ref "U1") (pin "26") (pinfunction "SCL_26") (pintype "bidirectional"))
      (node (ref "U2") (pin "26") (pinfunction "SCL_26") (pintype "bidirectional"))
      (node (ref "U3") (pin "26") (pinfunction "SCL_26") (pintype "bidirectional"))
      (node (ref "U5") (pin "P$7") (pinfunction "P1_7_P$7") (pintype "bidirectional"))
    )
    (net (code "101") (name "unconnected-(U$1-PROG-Pad5)") (class "Default")
      (node (ref "U$1") (pin "5") (pinfunction "PROG_5") (pintype "bidirectional"))
    )
    (net (code "102") (name "unconnected-(U$1-STAT-Pad1)") (class "Default")
      (node (ref "U$1") (pin "1") (pinfunction "STAT_1") (pintype "bidirectional"))
    )
    (net (code "103") (name "unconnected-(U$1-VBAT-Pad3)") (class "Default")
      (node (ref "U$1") (pin "3") (pinfunction "VBAT_3") (pintype "bidirectional"))
    )
    (net (code "104") (name "unconnected-(U$1-VDD-Pad4)") (class "Default")
      (node (ref "U$1") (pin "4") (pinfunction "VDD_4") (pintype "bidirectional"))
    )
    (net (code "105") (name "unconnected-(U$1-VSS-Pad2)") (class "Default")
      (node (ref "U$1") (pin "2") (pinfunction "VSS_2") (pintype "bidirectional"))
    )
    (net (code "106") (name "unconnected-(U$2-ADJ-Pad7)") (class "Default")
      (node (ref "U$2") (pin "7") (pinfunction "ADJ_7") (pintype "bidirectional"))
    )
    (net (code "107") (name "unconnected-(U$2-CDLY-Pad6)") (class "Default")
      (node (ref "U$2") (pin "6") (pinfunction "CDLY_6") (pintype "bidirectional"))
    )
    (net (code "108") (name "unconnected-(U$2-GND-Pad4)") (class "Default")
      (node (ref "U$2") (pin "4") (pinfunction "GND_4") (pintype "bidirectional"))
    )
    (net (code "109") (name "unconnected-(U$2-PWRGD-Pad5)") (class "Default")
      (node (ref "U$2") (pin "5") (pinfunction "PWRGD_5") (pintype "bidirectional"))
    )
    (net (code "110") (name "unconnected-(U$2-VIN-Pad1)") (class "Default")
      (node (ref "U$2") (pin "1") (pinfunction "VIN_1") (pintype "bidirectional"))
    )
    (net (code "111") (name "unconnected-(U$2-VIN-Pad2)") (class "Default")
      (node (ref "U$2") (pin "2") (pinfunction "VIN_2") (pintype "bidirectional"))
    )
    (net (code "112") (name "unconnected-(U$2-VOUT-Pad8)") (class "Default")
      (node (ref "U$2") (pin "8") (pinfunction "VOUT_8") (pintype "bidirectional"))
    )
    (net (code "113") (name "unconnected-(U$2-~{SHDN}-Pad3)") (class "Default")
      (node (ref "U$2") (pin "3") (pinfunction "~{SHDN}_3") (pintype "bidirectional"))
    )
    (net (code "114") (name "unconnected-(U5-P0_0-PadP$28)") (class "Default")
      (node (ref "U5") (pin "P$28") (pinfunction "P0_0_P$28") (pintype "bidirectional"))
    )
    (net (code "115") (name "unconnected-(U5-P0_1-PadP$27)") (class "Default")
      (node (ref "U5") (pin "P$27") (pinfunction "P0_1_P$27") (pintype "bidirectional"))
    )
    (net (code "116") (name "unconnected-(U5-P0_2-PadP$26)") (class "Default")
      (node (ref "U5") (pin "P$26") (pinfunction "P0_2_P$26") (pintype "bidirectional"))
    )
    (net (code "117") (name "unconnected-(U5-P0_3-PadP$25)") (class "Default")
      (node (ref "U5") (pin "P$25") (pinfunction "P0_3_P$25") (pintype "bidirectional"))
    )
    (net (code "118") (name "unconnected-(U5-P0_4-PadP$24)") (class "Default")
      (node (ref "U5") (pin "P$24") (pinfunction "P0_4_P$24") (pintype "bidirectional"))
    )
    (net (code "119") (name "unconnected-(U5-P0_5-PadP$23)") (class "Default")
      (node (ref "U5") (pin "P$23") (pinfunction "P0_5_P$23") (pintype "bidirectional"))
    )
    (net (code "120") (name "unconnected-(U5-P0_6-PadP$22)") (class "Default")
      (node (ref "U5") (pin "P$22") (pinfunction "P0_6_P$22") (pintype "bidirectional"))
    )
    (net (code "121") (name "unconnected-(U5-P0_7-PadP$19)") (class "Default")
      (node (ref "U5") (pin "P$19") (pinfunction "P0_7_P$19") (pintype "bidirectional"))
    )
    (net (code "122") (name "unconnected-(U5-P1_0-PadP$18)") (class "Default")
      (node (ref "U5") (pin "P$18") (pinfunction "P1_0_P$18") (pintype "bidirectional"))
    )
    (net (code "123") (name "unconnected-(U5-P1_1-PadP$17)") (class "Default")
      (node (ref "U5") (pin "P$17") (pinfunction "P1_1_P$17") (pintype "bidirectional"))
    )
    (net (code "124") (name "unconnected-(U5-P1_2-PadP$16)") (class "Default")
      (node (ref "U5") (pin "P$16") (pinfunction "P1_2_P$16") (pintype "bidirectional"))
    )
    (net (code "125") (name "unconnected-(U5-P1_3-PadP$15)") (class "Default")
      (node (ref "U5") (pin "P$15") (pinfunction "P1_3_P$15") (pintype "bidirectional"))
    )
    (net (code "126") (name "unconnected-(U5-P1_4-PadP$14)") (class "Default")
      (node (ref "U5") (pin "P$14") (pinfunction "P1_4_P$14") (pintype "bidirectional"))
    )
    (net (code "127") (name "unconnected-(U5-P1_5-PadP$13)") (class "Default")
      (node (ref "U5") (pin "P$13") (pinfunction "P1_5_P$13") (pintype "bidirectional"))
    )
    (net (code "128") (name "unconnected-(U5-P2_0-PadP$6)") (class "Default")
      (node (ref "U5") (pin "P$6") (pinfunction "P2_0_P$6") (pintype "bidirectional"))
    )
    (net (code "129") (name "unconnected-(U5-P2_1-PadP$5)") (class "Default")
      (node (ref "U5") (pin "P$5") (pinfunction "P2_1_P$5") (pintype "bidirectional"))
    )
    (net (code "130") (name "unconnected-(U5-P2_2-PadP$4)") (class "Default")
      (node (ref "U5") (pin "P$4") (pinfunction "P2_2_P$4") (pintype "bidirectional"))
    )
    (net (code "131") (name "unconnected-(U5-RESET-PadP$29)") (class "Default")
      (node (ref "U5") (pin "P$29") (pinfunction "RESET_P$29") (pintype "bidirectional"))
    )
    (net (code "132") (name "unconnected-(U5-USB+-PadP$11)") (class "Default")
      (node (ref "U5") (pin "P$11") (pinfunction "USB+_P$11") (pintype "bidirectional"))
    )
    (net (code "133") (name "unconnected-(U5-USB--PadP$12)") (class "Default")
      (node (ref "U5") (pin "P$12") (pinfunction "USB-_P$12") (pintype "bidirectional"))
    )
  )
)
